# 2_isoSPI.net
KiCad netlist of a schematic drawn in Altium Designer
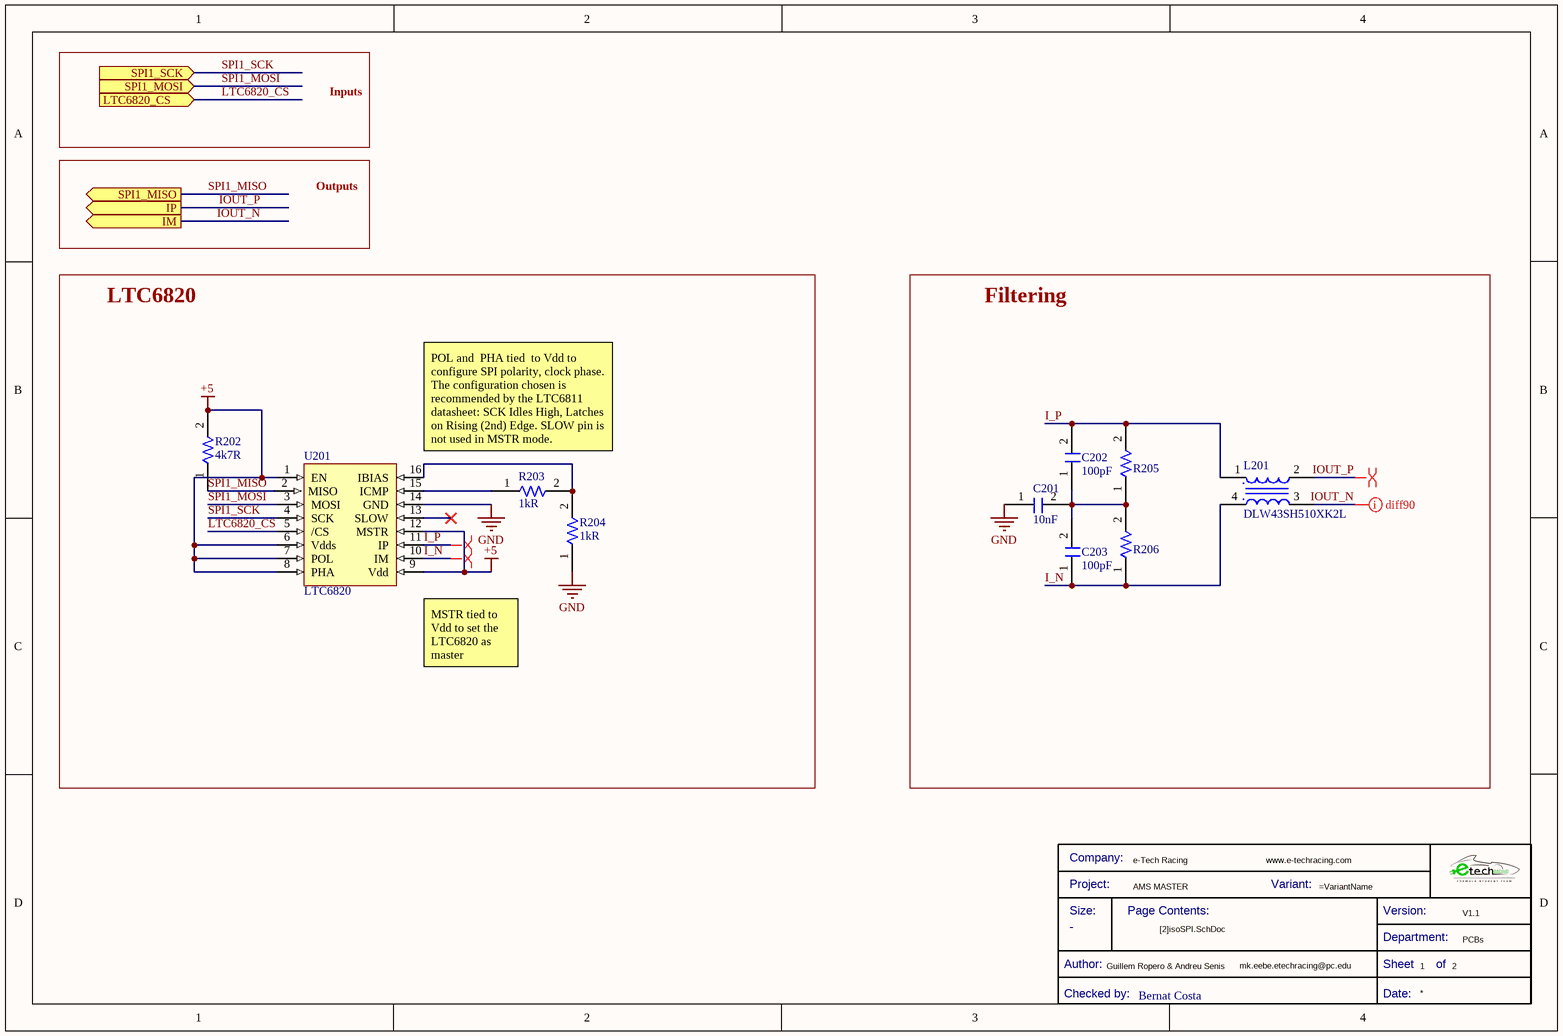
[diagram p0: [2]isoSPI.SchDoc]

(export (version "E")
  (design (tool "Eeschema 10.0.6"))
  (components
    (comp (ref "C201")
      (value "885012008055")
      (footprint "C1206FNPC-RW")
      (description "Cap Cer 10000PF 50V C0G/NP0 1206")
      (fields
        (field (name "MANUFACTURER") "Wurth Electronics")
        (field (name "TOLERANCE") "5%")
        (field (name "CAPACITANCE") "10nF")
        (field (name ".CREATOR") "DO")
      )
      (libsource (lib "Passives") (part "C10n-50V-1206FNPC-C0G/NP0"))
    )
    (comp (ref "C202")
      (value "885012007057")
      (footprint "C0805FNPC-W")
      (fields
        (field (name "MANUFACTURER") "Wurth Electronics")
        (field (name "TOLERANCE") "5%")
        (field (name "CAPACITANCE") "100pF")
        (field (name ".CREATOR") "DR")
      )
      (libsource (lib "Passives") (part "C100p-50V-0805FNPC-C0G/NP0"))
    )
    (comp (ref "C203")
      (value "885012007057")
      (footprint "C0805FNPC-W")
      (fields
        (field (name "MANUFACTURER") "Wurth Electronics")
        (field (name "TOLERANCE") "5%")
        (field (name "CAPACITANCE") "100pF")
        (field (name ".CREATOR") "DR")
      )
      (libsource (lib "Passives") (part "C100p-50V-0805FNPC-C0G/NP0"))
    )
    (comp (ref "L201")
      (value "CMC-51uH-DLW43SH510XK2L")
      (footprint "CMC-51uH-230mA")
      (description "Ind Common Mode Choke Wirewound 51uH -30% to 50% 1MHz 230mA 1812 Embossed Plastic T/R")
      (fields
        (field (name "MANUFACTURER") "Murata")
        (field (name "MANUFACTURER PART NUMBER") "DLW43SH510XK2L")
        (field (name "SUPPLIER PART NUMBER 1") "DLW43SH510XK2L")
      )
      (libsource (lib "Filter components") (part "CMC-51uH-230mA"))
    )
    (comp (ref "R202")
      (value "CR0805-JW-472ELF")
      (footprint "R0805FTK")
      (description "Res Thick Film 0805 4.7K Ohm 5% 1/8W ±200ppm/°C Molded SMD SMD Paper Tape on Plastic Reel")
      (fields
        (field (name "TOLERANCE") "5%")
        (field (name "RESISTANCE") "4k7R")
        (field (name ".CREATOR") "DR")
      )
      (libsource (lib "Passives") (part "R4.7K-0805FTK"))
    )
    (comp (ref "R203")
      (value "CR0805-JW-102ELF")
      (footprint "R0805FTK")
      (description "Res Thick Film 0805 1K Ohm 5% 1/8W ±200ppm/°C Molded SMD SMD Paper Tape on Plastic Reel")
      (fields
        (field (name "TOLERANCE") "5%")
        (field (name "RESISTANCE") "1kR")
        (field (name ".CREATOR") "GP")
      )
      (libsource (lib "Passives") (part "R1k-0805FTK"))
    )
    (comp (ref "R204")
      (value "CR0805-JW-102ELF")
      (footprint "R0805FTK")
      (description "Res Thick Film 0805 1K Ohm 5% 1/8W ±200ppm/°C Molded SMD SMD Paper Tape on Plastic Reel")
      (fields
        (field (name "TOLERANCE") "5%")
        (field (name "RESISTANCE") "1kR")
        (field (name ".CREATOR") "GP")
      )
      (libsource (lib "Passives") (part "R1k-0805FTK"))
    )
    (comp (ref "R205")
      (value "CRCW080550R0FKTA")
      (footprint "R0805FTK")
      (description "Res Thick Film 0805 50 Ohm 1% 0.125W(1/8W) ±100ppm/C Pad SMD Automotive T/R")
      (fields (field (name "MANUFACTURER") "Vishay Dale") (field (name "TOLERANCE") "1%"))
      (libsource (lib "Passives") (part "R50-0805FTK"))
    )
    (comp (ref "R206")
      (value "CRCW080550R0FKTA")
      (footprint "R0805FTK")
      (description "Res Thick Film 0805 50 Ohm 1% 0.125W(1/8W) ±100ppm/C Pad SMD Automotive T/R")
      (fields (field (name "MANUFACTURER") "Vishay Dale") (field (name "TOLERANCE") "1%"))
      (libsource (lib "Passives") (part "R50-0805FTK"))
    )
    (comp (ref "U201")
      (value "LTC6820")
      (footprint "LTC6820")
      (libsource (lib "Integrated circuits") (part "U_LTC6820"))
    )
  )
  (nets
    (net (code "1") (name "+5") (class "Default")
      (node (ref "R202") (pin "2") (pinfunction "2_2") (pintype "passive"))
      (node (ref "U201") (pin "1") (pinfunction "EN_1") (pintype "input"))
      (node (ref "U201") (pin "12") (pinfunction "MSTR_12") (pintype "input"))
      (node (ref "U201") (pin "6") (pinfunction "Vdds_6") (pintype "input"))
      (node (ref "U201") (pin "7") (pinfunction "POL_7") (pintype "input"))
      (node (ref "U201") (pin "8") (pinfunction "PHA_8") (pintype "input"))
      (node (ref "U201") (pin "9") (pinfunction "Vdd_9") (pintype "input"))
    )
    (net (code "2") (name "/IOUT_N") (class "Default")
      (node (ref "L201") (pin "3") (pinfunction "3_OUT_3") (pintype "passive"))
    )
    (net (code "3") (name "/IOUT_P") (class "Default")
      (node (ref "L201") (pin "2") (pinfunction "2_OUT_2") (pintype "passive"))
    )
    (net (code "4") (name "/I_N") (class "Default")
      (node (ref "C203") (pin "1") (pinfunction "1_1") (pintype "passive"))
      (node (ref "L201") (pin "4") (pinfunction "4_IN_4") (pintype "passive"))
      (node (ref "R206") (pin "1") (pinfunction "1_1") (pintype "passive"))
      (node (ref "U201") (pin "10") (pinfunction "IM_10") (pintype "input"))
    )
    (net (code "5") (name "/I_P") (class "Default")
      (node (ref "C202") (pin "2") (pinfunction "2_2") (pintype "passive"))
      (node (ref "L201") (pin "1") (pinfunction "1_IN_1") (pintype "passive"))
      (node (ref "R205") (pin "2") (pinfunction "2_2") (pintype "passive"))
      (node (ref "U201") (pin "11") (pinfunction "IP_11") (pintype "input"))
    )
    (net (code "6") (name "/LTC6820_CS") (class "Default")
      (node (ref "U201") (pin "5") (pinfunction "/CS_5") (pintype "input"))
    )
    (net (code "7") (name "/SPI1_MISO") (class "Default")
      (node (ref "R202") (pin "1") (pinfunction "1_1") (pintype "passive"))
      (node (ref "U201") (pin "2") (pinfunction "MISO_2") (pintype "input"))
    )
    (net (code "8") (name "/SPI1_MOSI") (class "Default")
      (node (ref "U201") (pin "3") (pinfunction "MOSI_3") (pintype "input"))
    )
    (net (code "9") (name "/SPI1_SCK") (class "Default")
      (node (ref "U201") (pin "4") (pinfunction "SCK_4") (pintype "input"))
    )
    (net (code "10") (name "GND") (class "Default")
      (node (ref "C201") (pin "1") (pinfunction "1_1") (pintype "passive"))
      (node (ref "R204") (pin "1") (pinfunction "1_1") (pintype "passive"))
      (node (ref "U201") (pin "14") (pinfunction "GND_14") (pintype "input"))
    )
    (net (code "11") (name "Net-(C201-Pad2)") (class "Default")
      (node (ref "C201") (pin "2") (pinfunction "2_2") (pintype "passive"))
      (node (ref "C202") (pin "1") (pinfunction "1_1") (pintype "passive"))
      (node (ref "C203") (pin "2") (pinfunction "2_2") (pintype "passive"))
      (node (ref "R205") (pin "1") (pinfunction "1_1") (pintype "passive"))
      (node (ref "R206") (pin "2") (pinfunction "2_2") (pintype "passive"))
    )
    (net (code "12") (name "Net-(U201-IBIAS)") (class "Default")
      (node (ref "R203") (pin "2") (pinfunction "2_2") (pintype "passive"))
      (node (ref "R204") (pin "2") (pinfunction "2_2") (pintype "passive"))
      (node (ref "U201") (pin "16") (pinfunction "IBIAS_16") (pintype "input"))
    )
    (net (code "13") (name "Net-(U201-ICMP)") (class "Default")
      (node (ref "R203") (pin "1") (pinfunction "1_1") (pintype "passive"))
      (node (ref "U201") (pin "15") (pinfunction "ICMP_15") (pintype "input"))
    )
    (net (code "14") (name "unconnected-(U201-SLOW-Pad13)") (class "Default")
      (node (ref "U201") (pin "13") (pinfunction "SLOW_13") (pintype "input+no_connect"))
    )
  )
)
